# power.net
KiCad netlist of a schematic drawn in EAGLE
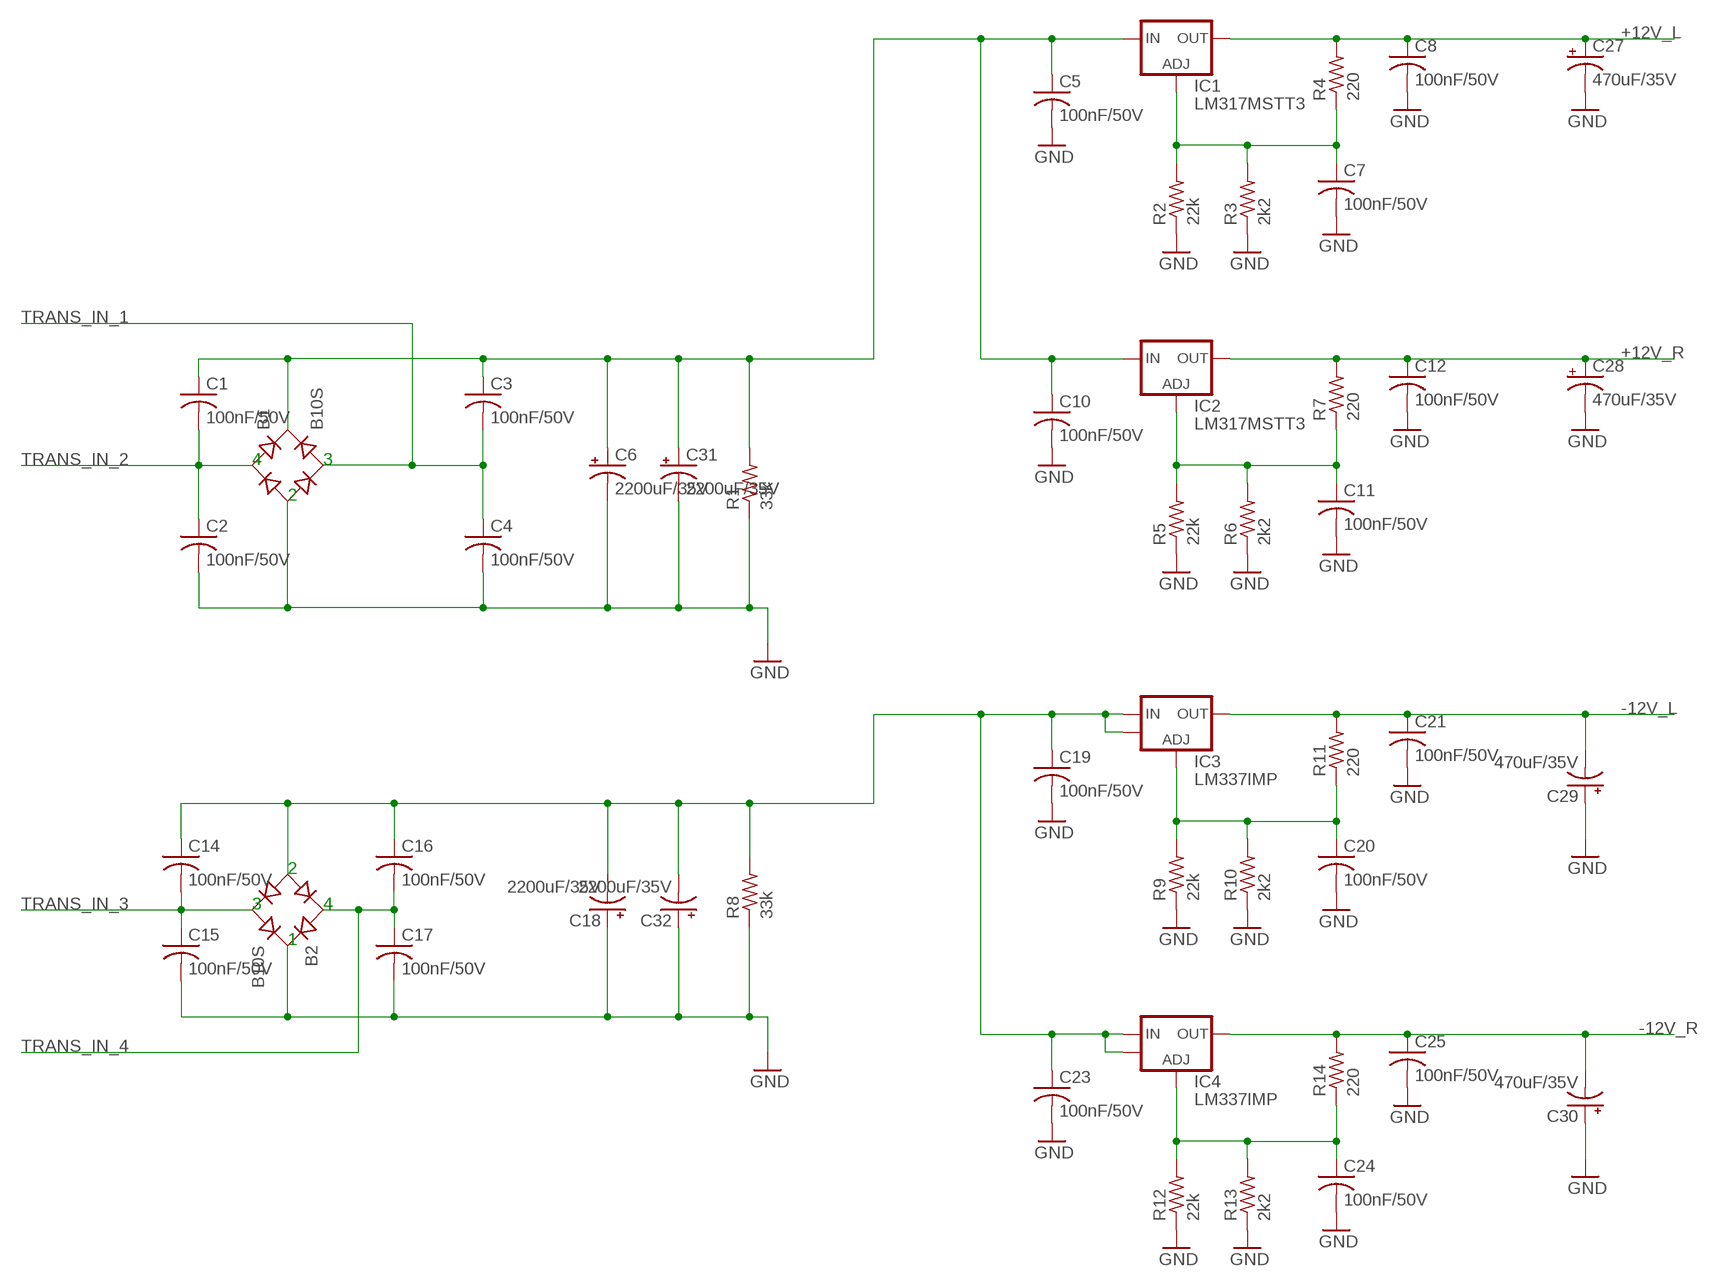
[diagram p0: schematic, sheet 1]

(export (version "E")
  (design (tool "Eeschema 10.0.6"))
  (components
    (comp (ref "B1")
      (value "B10S")
      (footprint "eagle-import:MBS")
      (libsource (lib "eagle-import") (part "BS10"))
    )
    (comp (ref "B2")
      (value "B10S")
      (footprint "eagle-import:MBS")
      (libsource (lib "eagle-import") (part "BS10"))
    )
    (comp (ref "C1")
      (value "100nF/50V")
      (footprint "eagle-import:C0805")
      (libsource (lib "eagle-import") (part "C-USC0805"))
    )
    (comp (ref "C2")
      (value "100nF/50V")
      (footprint "eagle-import:C0805")
      (libsource (lib "eagle-import") (part "C-USC0805"))
    )
    (comp (ref "C3")
      (value "100nF/50V")
      (footprint "eagle-import:C0805")
      (libsource (lib "eagle-import") (part "C-USC0805"))
    )
    (comp (ref "C4")
      (value "100nF/50V")
      (footprint "eagle-import:C0805")
      (libsource (lib "eagle-import") (part "C-USC0805"))
    )
    (comp (ref "C5")
      (value "100nF/50V")
      (footprint "eagle-import:C0805")
      (libsource (lib "eagle-import") (part "C-USC0805"))
    )
    (comp (ref "C6")
      (value "2200uF/35V")
      (footprint "eagle-import:E5-13")
      (libsource (lib "eagle-import") (part "CPOL-USE5-13"))
    )
    (comp (ref "C7")
      (value "100nF/50V")
      (footprint "eagle-import:C0805")
      (libsource (lib "eagle-import") (part "C-USC0805"))
    )
    (comp (ref "C8")
      (value "100nF/50V")
      (footprint "eagle-import:C0805")
      (libsource (lib "eagle-import") (part "C-USC0805"))
    )
    (comp (ref "C10")
      (value "100nF/50V")
      (footprint "eagle-import:C0805")
      (libsource (lib "eagle-import") (part "C-USC0805"))
    )
    (comp (ref "C11")
      (value "100nF/50V")
      (footprint "eagle-import:C0805")
      (libsource (lib "eagle-import") (part "C-USC0805"))
    )
    (comp (ref "C12")
      (value "100nF/50V")
      (footprint "eagle-import:C0805")
      (libsource (lib "eagle-import") (part "C-USC0805"))
    )
    (comp (ref "C14")
      (value "100nF/50V")
      (footprint "eagle-import:C0805")
      (libsource (lib "eagle-import") (part "C-USC0805"))
    )
    (comp (ref "C15")
      (value "100nF/50V")
      (footprint "eagle-import:C0805")
      (libsource (lib "eagle-import") (part "C-USC0805"))
    )
    (comp (ref "C16")
      (value "100nF/50V")
      (footprint "eagle-import:C0805")
      (libsource (lib "eagle-import") (part "C-USC0805"))
    )
    (comp (ref "C17")
      (value "100nF/50V")
      (footprint "eagle-import:C0805")
      (libsource (lib "eagle-import") (part "C-USC0805"))
    )
    (comp (ref "C18")
      (value "2200uF/35V")
      (footprint "eagle-import:E5-13")
      (libsource (lib "eagle-import") (part "CPOL-USE5-13"))
    )
    (comp (ref "C19")
      (value "100nF/50V")
      (footprint "eagle-import:C0805")
      (libsource (lib "eagle-import") (part "C-USC0805"))
    )
    (comp (ref "C20")
      (value "100nF/50V")
      (footprint "eagle-import:C0805")
      (libsource (lib "eagle-import") (part "C-USC0805"))
    )
    (comp (ref "C21")
      (value "100nF/50V")
      (footprint "eagle-import:C0805")
      (libsource (lib "eagle-import") (part "C-USC0805"))
    )
    (comp (ref "C23")
      (value "100nF/50V")
      (footprint "eagle-import:C0805")
      (libsource (lib "eagle-import") (part "C-USC0805"))
    )
    (comp (ref "C24")
      (value "100nF/50V")
      (footprint "eagle-import:C0805")
      (libsource (lib "eagle-import") (part "C-USC0805"))
    )
    (comp (ref "C25")
      (value "100nF/50V")
      (footprint "eagle-import:C0805")
      (libsource (lib "eagle-import") (part "C-USC0805"))
    )
    (comp (ref "C27")
      (value "470uF/35V")
      (footprint "eagle-import:E5-13")
      (libsource (lib "eagle-import") (part "CPOL-USE5-13"))
    )
    (comp (ref "C28")
      (value "470uF/35V")
      (footprint "eagle-import:E5-13")
      (libsource (lib "eagle-import") (part "CPOL-USE5-13"))
    )
    (comp (ref "C29")
      (value "470uF/35V")
      (footprint "eagle-import:E5-13")
      (libsource (lib "eagle-import") (part "CPOL-USE5-13"))
    )
    (comp (ref "C30")
      (value "470uF/35V")
      (footprint "eagle-import:E5-13")
      (libsource (lib "eagle-import") (part "CPOL-USE5-13"))
    )
    (comp (ref "C31")
      (value "2200uF/35V")
      (footprint "eagle-import:E5-13")
      (libsource (lib "eagle-import") (part "CPOL-USE5-13"))
    )
    (comp (ref "C32")
      (value "2200uF/35V")
      (footprint "eagle-import:E5-13")
      (libsource (lib "eagle-import") (part "CPOL-USE5-13"))
    )
    (comp (ref "IC1")
      (value "LM317MSTT3")
      (footprint "eagle-import:SOT223")
      (libsource (lib "eagle-import") (part "LM317?MSTT3"))
    )
    (comp (ref "IC2")
      (value "LM317MSTT3")
      (footprint "eagle-import:SOT223")
      (libsource (lib "eagle-import") (part "LM317?MSTT3"))
    )
    (comp (ref "IC3")
      (value "LM337IMP")
      (footprint "eagle-import:SOT-223")
      (libsource (lib "eagle-import") (part "LM337IMP"))
    )
    (comp (ref "IC4")
      (value "LM337IMP")
      (footprint "eagle-import:SOT-223")
      (libsource (lib "eagle-import") (part "LM337IMP"))
    )
    (comp (ref "R1")
      (value "33k")
      (footprint "eagle-import:M0805")
      (libsource (lib "eagle-import") (part "R-US_M0805"))
    )
    (comp (ref "R2")
      (value "22k")
      (footprint "eagle-import:M0805")
      (libsource (lib "eagle-import") (part "R-US_M0805"))
    )
    (comp (ref "R3")
      (value "2k2")
      (footprint "eagle-import:M0805")
      (libsource (lib "eagle-import") (part "R-US_M0805"))
    )
    (comp (ref "R4")
      (value "220")
      (footprint "eagle-import:M0805")
      (libsource (lib "eagle-import") (part "R-US_M0805"))
    )
    (comp (ref "R5")
      (value "22k")
      (footprint "eagle-import:M0805")
      (libsource (lib "eagle-import") (part "R-US_M0805"))
    )
    (comp (ref "R6")
      (value "2k2")
      (footprint "eagle-import:M0805")
      (libsource (lib "eagle-import") (part "R-US_M0805"))
    )
    (comp (ref "R7")
      (value "220")
      (footprint "eagle-import:M0805")
      (libsource (lib "eagle-import") (part "R-US_M0805"))
    )
    (comp (ref "R8")
      (value "33k")
      (footprint "eagle-import:M0805")
      (libsource (lib "eagle-import") (part "R-US_M0805"))
    )
    (comp (ref "R9")
      (value "22k")
      (footprint "eagle-import:M0805")
      (libsource (lib "eagle-import") (part "R-US_M0805"))
    )
    (comp (ref "R10")
      (value "2k2")
      (footprint "eagle-import:M0805")
      (libsource (lib "eagle-import") (part "R-US_M0805"))
    )
    (comp (ref "R11")
      (value "220")
      (footprint "eagle-import:M0805")
      (libsource (lib "eagle-import") (part "R-US_M0805"))
    )
    (comp (ref "R12")
      (value "22k")
      (footprint "eagle-import:M0805")
      (libsource (lib "eagle-import") (part "R-US_M0805"))
    )
    (comp (ref "R13")
      (value "2k2")
      (footprint "eagle-import:M0805")
      (libsource (lib "eagle-import") (part "R-US_M0805"))
    )
    (comp (ref "R14")
      (value "220")
      (footprint "eagle-import:M0805")
      (libsource (lib "eagle-import") (part "R-US_M0805"))
    )
  )
  (nets
    (net (code "1") (name "/+12V_L") (class "Default")
      (node (ref "C27") (pin "+") (pinfunction "+_+") (pintype "passive"))
      (node (ref "C8") (pin "1") (pinfunction "1_1") (pintype "passive"))
      (node (ref "IC1") (pin "4") (pinfunction "OUT_4") (pintype "passive"))
      (node (ref "R4") (pin "2") (pinfunction "2_2") (pintype "passive"))
    )
    (net (code "2") (name "/+12V_R") (class "Default")
      (node (ref "C12") (pin "1") (pinfunction "1_1") (pintype "passive"))
      (node (ref "C28") (pin "+") (pinfunction "+_+") (pintype "passive"))
      (node (ref "IC2") (pin "4") (pinfunction "OUT_4") (pintype "passive"))
      (node (ref "R7") (pin "2") (pinfunction "2_2") (pintype "passive"))
    )
    (net (code "3") (name "/-12V_L") (class "Default")
      (node (ref "C21") (pin "1") (pinfunction "1_1") (pintype "passive"))
      (node (ref "C29") (pin "-") (pinfunction "-_-") (pintype "passive"))
      (node (ref "IC3") (pin "3") (pinfunction "OUT_3") (pintype "passive"))
      (node (ref "R11") (pin "2") (pinfunction "2_2") (pintype "passive"))
    )
    (net (code "4") (name "/-12V_R") (class "Default")
      (node (ref "C25") (pin "1") (pinfunction "1_1") (pintype "passive"))
      (node (ref "C30") (pin "-") (pinfunction "-_-") (pintype "passive"))
      (node (ref "IC4") (pin "3") (pinfunction "OUT_3") (pintype "passive"))
      (node (ref "R14") (pin "2") (pinfunction "2_2") (pintype "passive"))
    )
    (net (code "5") (name "/TRANS_IN_1") (class "Default")
      (node (ref "B1") (pin "AC2") (pinfunction "AC2_AC2") (pintype "passive"))
      (node (ref "C3") (pin "2") (pinfunction "2_2") (pintype "passive"))
      (node (ref "C4") (pin "1") (pinfunction "1_1") (pintype "passive"))
    )
    (net (code "6") (name "/TRANS_IN_2") (class "Default")
      (node (ref "B1") (pin "AC1") (pinfunction "AC1_AC1") (pintype "passive"))
      (node (ref "C1") (pin "2") (pinfunction "2_2") (pintype "passive"))
      (node (ref "C2") (pin "1") (pinfunction "1_1") (pintype "passive"))
    )
    (net (code "7") (name "/TRANS_IN_3") (class "Default")
      (node (ref "B2") (pin "AC2") (pinfunction "AC2_AC2") (pintype "passive"))
      (node (ref "C14") (pin "2") (pinfunction "2_2") (pintype "passive"))
      (node (ref "C15") (pin "1") (pinfunction "1_1") (pintype "passive"))
    )
    (net (code "8") (name "/TRANS_IN_4") (class "Default")
      (node (ref "B2") (pin "AC1") (pinfunction "AC1_AC1") (pintype "passive"))
      (node (ref "C16") (pin "2") (pinfunction "2_2") (pintype "passive"))
      (node (ref "C17") (pin "1") (pinfunction "1_1") (pintype "passive"))
    )
    (net (code "9") (name "GND") (class "Default")
      (node (ref "B1") (pin "-") (pinfunction "-_-") (pintype "passive"))
      (node (ref "B2") (pin "+") (pinfunction "+_+") (pintype "passive"))
      (node (ref "C10") (pin "2") (pinfunction "2_2") (pintype "passive"))
      (node (ref "C11") (pin "2") (pinfunction "2_2") (pintype "passive"))
      (node (ref "C12") (pin "2") (pinfunction "2_2") (pintype "passive"))
      (node (ref "C15") (pin "2") (pinfunction "2_2") (pintype "passive"))
      (node (ref "C17") (pin "2") (pinfunction "2_2") (pintype "passive"))
      (node (ref "C18") (pin "+") (pinfunction "+_+") (pintype "passive"))
      (node (ref "C19") (pin "2") (pinfunction "2_2") (pintype "passive"))
      (node (ref "C2") (pin "2") (pinfunction "2_2") (pintype "passive"))
      (node (ref "C20") (pin "2") (pinfunction "2_2") (pintype "passive"))
      (node (ref "C21") (pin "2") (pinfunction "2_2") (pintype "passive"))
      (node (ref "C23") (pin "2") (pinfunction "2_2") (pintype "passive"))
      (node (ref "C24") (pin "2") (pinfunction "2_2") (pintype "passive"))
      (node (ref "C25") (pin "2") (pinfunction "2_2") (pintype "passive"))
      (node (ref "C27") (pin "-") (pinfunction "-_-") (pintype "passive"))
      (node (ref "C28") (pin "-") (pinfunction "-_-") (pintype "passive"))
      (node (ref "C29") (pin "+") (pinfunction "+_+") (pintype "passive"))
      (node (ref "C30") (pin "+") (pinfunction "+_+") (pintype "passive"))
      (node (ref "C31") (pin "-") (pinfunction "-_-") (pintype "passive"))
      (node (ref "C32") (pin "+") (pinfunction "+_+") (pintype "passive"))
      (node (ref "C4") (pin "2") (pinfunction "2_2") (pintype "passive"))
      (node (ref "C5") (pin "2") (pinfunction "2_2") (pintype "passive"))
      (node (ref "C6") (pin "-") (pinfunction "-_-") (pintype "passive"))
      (node (ref "C7") (pin "2") (pinfunction "2_2") (pintype "passive"))
      (node (ref "C8") (pin "2") (pinfunction "2_2") (pintype "passive"))
      (node (ref "R1") (pin "1") (pinfunction "1_1") (pintype "passive"))
      (node (ref "R10") (pin "1") (pinfunction "1_1") (pintype "passive"))
      (node (ref "R12") (pin "1") (pinfunction "1_1") (pintype "passive"))
      (node (ref "R13") (pin "1") (pinfunction "1_1") (pintype "passive"))
      (node (ref "R2") (pin "1") (pinfunction "1_1") (pintype "passive"))
      (node (ref "R3") (pin "1") (pinfunction "1_1") (pintype "passive"))
      (node (ref "R5") (pin "1") (pinfunction "1_1") (pintype "passive"))
      (node (ref "R6") (pin "1") (pinfunction "1_1") (pintype "passive"))
      (node (ref "R8") (pin "1") (pinfunction "1_1") (pintype "passive"))
      (node (ref "R9") (pin "1") (pinfunction "1_1") (pintype "passive"))
    )
    (net (code "10") (name "Net-(IC1-ADJ)") (class "Default")
      (node (ref "C7") (pin "1") (pinfunction "1_1") (pintype "passive"))
      (node (ref "IC1") (pin "1") (pinfunction "ADJ_1") (pintype "input"))
      (node (ref "R2") (pin "2") (pinfunction "2_2") (pintype "passive"))
      (node (ref "R3") (pin "2") (pinfunction "2_2") (pintype "passive"))
      (node (ref "R4") (pin "1") (pinfunction "1_1") (pintype "passive"))
    )
    (net (code "11") (name "Net-(IC1-IN)") (class "Default")
      (node (ref "B1") (pin "+") (pinfunction "+_+") (pintype "passive"))
      (node (ref "C1") (pin "1") (pinfunction "1_1") (pintype "passive"))
      (node (ref "C10") (pin "1") (pinfunction "1_1") (pintype "passive"))
      (node (ref "C3") (pin "1") (pinfunction "1_1") (pintype "passive"))
      (node (ref "C31") (pin "+") (pinfunction "+_+") (pintype "passive"))
      (node (ref "C5") (pin "1") (pinfunction "1_1") (pintype "passive"))
      (node (ref "C6") (pin "+") (pinfunction "+_+") (pintype "passive"))
      (node (ref "IC1") (pin "3") (pinfunction "IN_3") (pintype "input"))
      (node (ref "IC2") (pin "3") (pinfunction "IN_3") (pintype "input"))
      (node (ref "R1") (pin "2") (pinfunction "2_2") (pintype "passive"))
    )
    (net (code "12") (name "Net-(IC2-ADJ)") (class "Default")
      (node (ref "C11") (pin "1") (pinfunction "1_1") (pintype "passive"))
      (node (ref "IC2") (pin "1") (pinfunction "ADJ_1") (pintype "input"))
      (node (ref "R5") (pin "2") (pinfunction "2_2") (pintype "passive"))
      (node (ref "R6") (pin "2") (pinfunction "2_2") (pintype "passive"))
      (node (ref "R7") (pin "1") (pinfunction "1_1") (pintype "passive"))
    )
    (net (code "13") (name "Net-(IC3-ADJ)") (class "Default")
      (node (ref "C20") (pin "1") (pinfunction "1_1") (pintype "passive"))
      (node (ref "IC3") (pin "1") (pinfunction "ADJ_1") (pintype "input"))
      (node (ref "R10") (pin "2") (pinfunction "2_2") (pintype "passive"))
      (node (ref "R11") (pin "1") (pinfunction "1_1") (pintype "passive"))
      (node (ref "R9") (pin "2") (pinfunction "2_2") (pintype "passive"))
    )
    (net (code "14") (name "Net-(IC3-IN)") (class "Default")
      (node (ref "B2") (pin "-") (pinfunction "-_-") (pintype "passive"))
      (node (ref "C14") (pin "1") (pinfunction "1_1") (pintype "passive"))
      (node (ref "C16") (pin "1") (pinfunction "1_1") (pintype "passive"))
      (node (ref "C18") (pin "-") (pinfunction "-_-") (pintype "passive"))
      (node (ref "C19") (pin "1") (pinfunction "1_1") (pintype "passive"))
      (node (ref "C23") (pin "1") (pinfunction "1_1") (pintype "passive"))
      (node (ref "C32") (pin "-") (pinfunction "-_-") (pintype "passive"))
      (node (ref "IC3") (pin "2") (pinfunction "IN_2") (pintype "input"))
      (node (ref "IC3") (pin "4") (pinfunction "P$1_4") (pintype "bidirectional"))
      (node (ref "IC4") (pin "2") (pinfunction "IN_2") (pintype "input"))
      (node (ref "IC4") (pin "4") (pinfunction "P$1_4") (pintype "bidirectional"))
      (node (ref "R8") (pin "2") (pinfunction "2_2") (pintype "passive"))
    )
    (net (code "15") (name "Net-(IC4-ADJ)") (class "Default")
      (node (ref "C24") (pin "1") (pinfunction "1_1") (pintype "passive"))
      (node (ref "IC4") (pin "1") (pinfunction "ADJ_1") (pintype "input"))
      (node (ref "R12") (pin "2") (pinfunction "2_2") (pintype "passive"))
      (node (ref "R13") (pin "2") (pinfunction "2_2") (pintype "passive"))
      (node (ref "R14") (pin "1") (pinfunction "1_1") (pintype "passive"))
    )
  )
)
